# Regulator.net
KiCad netlist of a schematic drawn in Altium Designer
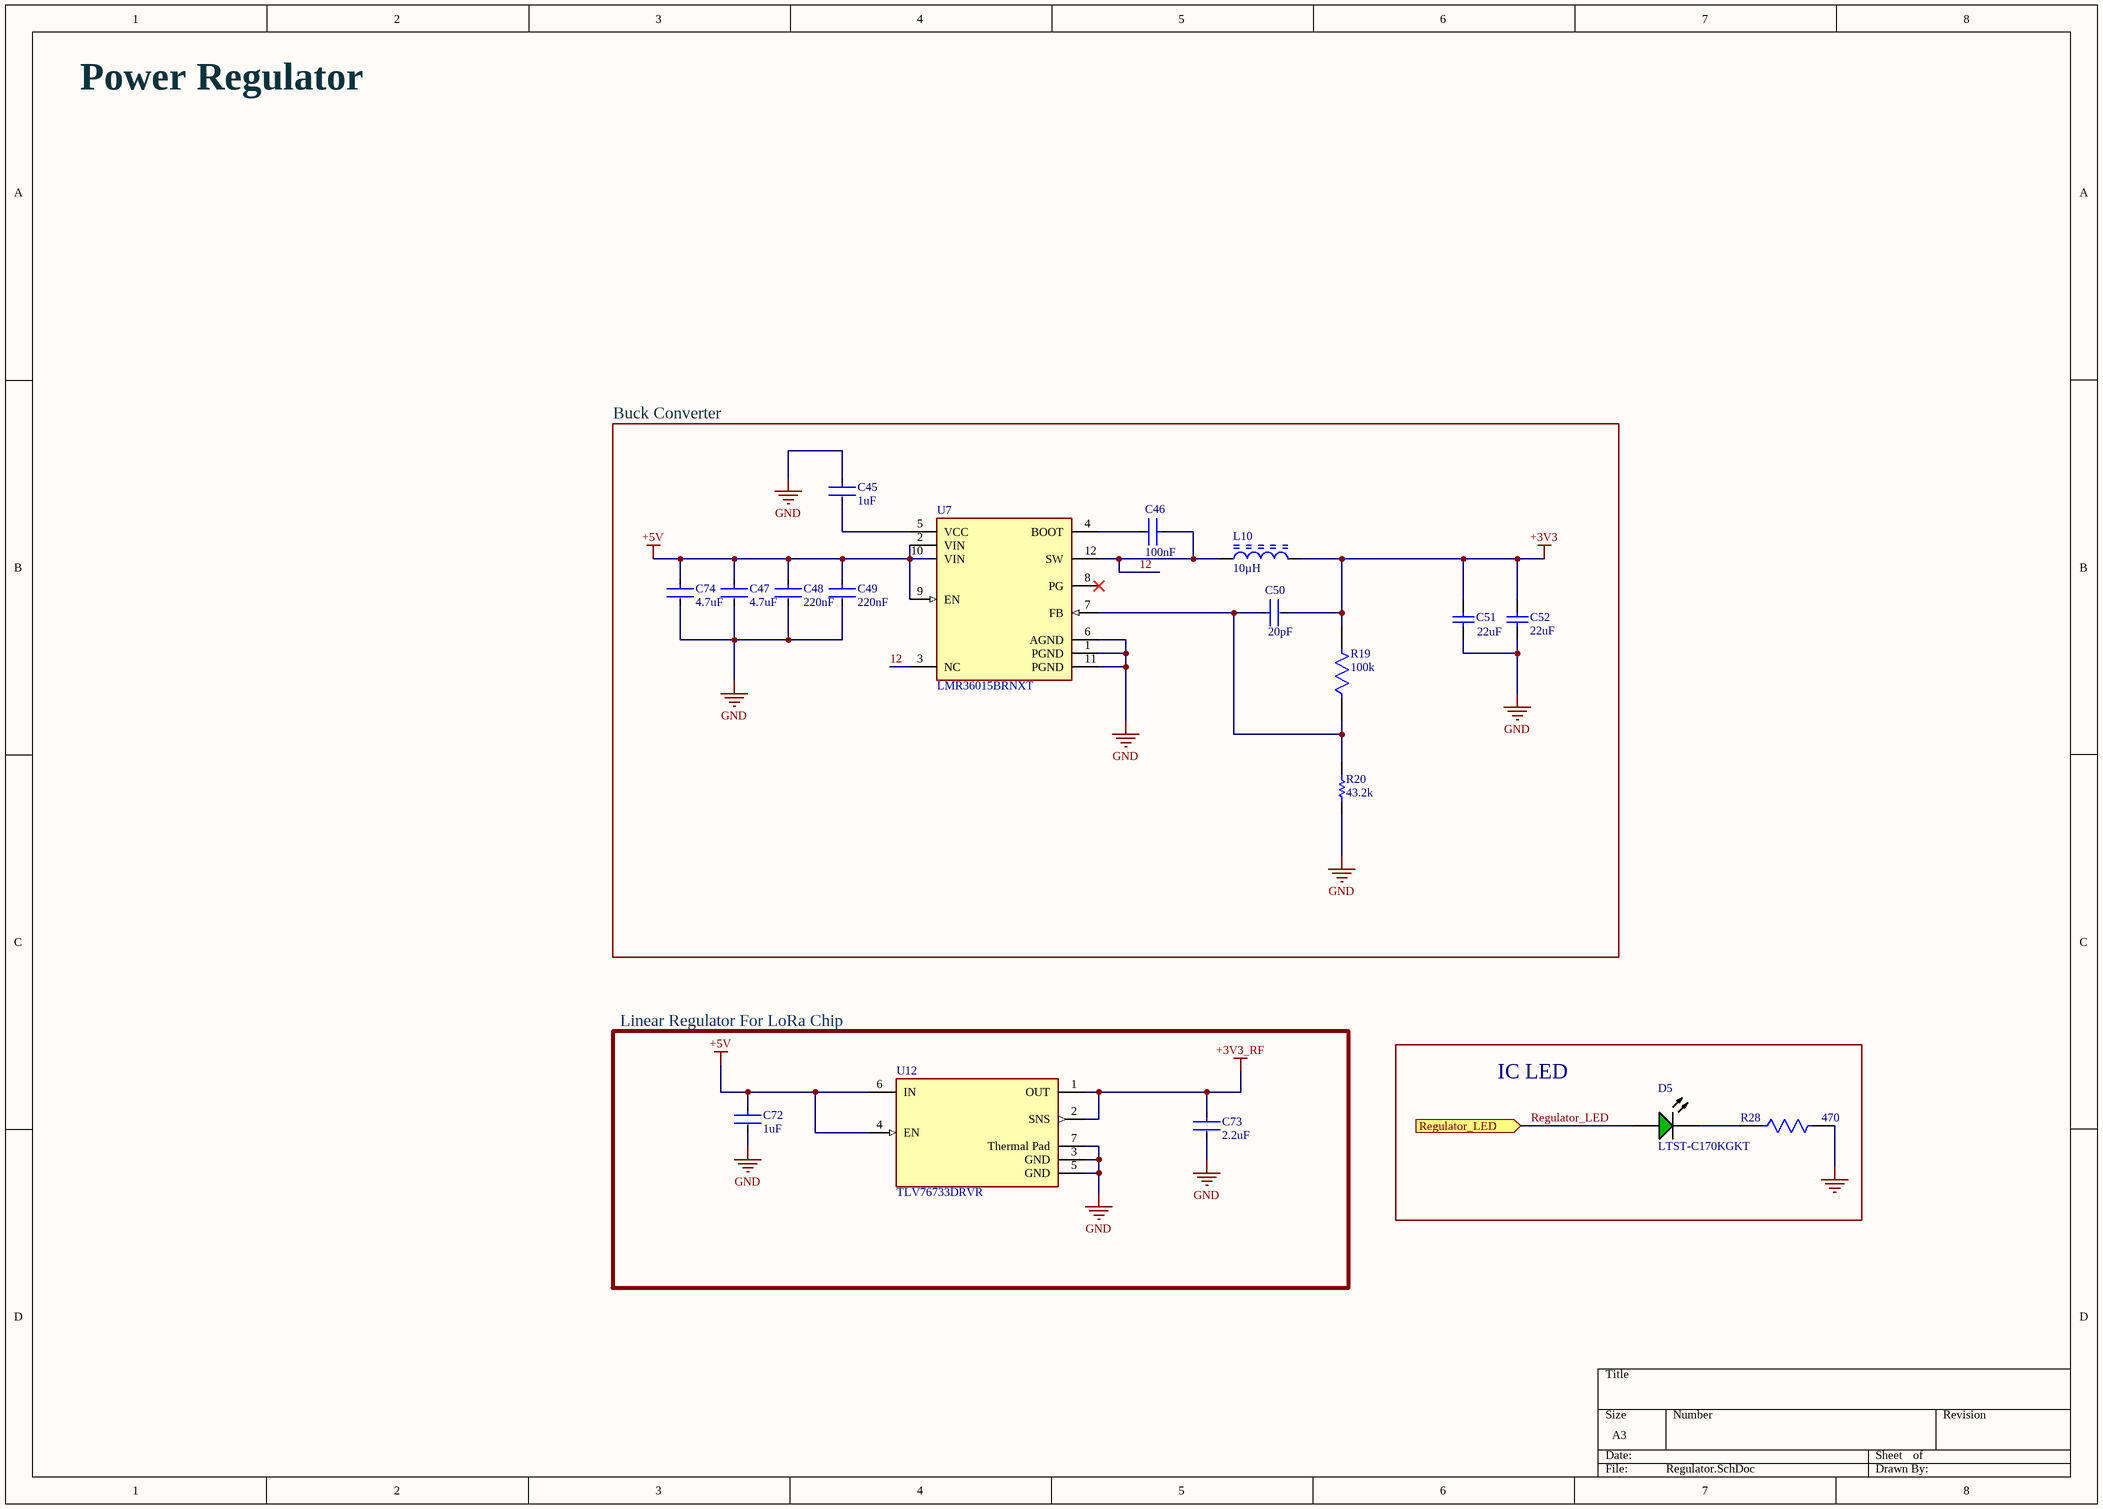
[diagram p0: Regulator.SchDoc]

(export (version "E")
  (design (tool "Eeschema 10.0.6"))
  (components
    (comp (ref "C45")
      (value "1uF")
      (footprint "FP-C0603C105K4PACTU-MFG")
      (description "CAP CER 1UF 16V X5R 0603")
      (fields (field (name "TOLERANCE") "10%") (field (name "VOLTAGE") "16V"))
      (libsource (lib "Altium Content Vault") (part "b4654b650e69147ec39a6b967a45e02"))
    )
    (comp (ref "C46")
      (value "100nF")
      (footprint "FP-GRM15-MFG")
      (description "CAP CER 0.1UF 16V X7R 0402")
      (fields (field (name "MANUFACTURER PART NUMBER") "GRM155R71C104KA88D") (field (name "TOLERANCE") "10%"))
      (libsource (lib "Altium Content Vault") (part "236180d848d6139a670b325ea6854c9"))
    )
    (comp (ref "C47")
      (value "4.7uF")
      (footprint "FP-1210-L_3_3_0_4-W_2_5_0-IPC_B")
      (description "Automotive Ceramic Capacitor, 1210, 4.7uF, 10%, X7R, 15%, 16V")
      (fields (field (name "TOLERANCE") "10%"))
      (libsource (lib "Altium Content Vault") (part "02cd4be3c70576c341d710602a673aa"))
    )
    (comp (ref "C48")
      (value "220nF")
      (footprint "FP-GRM155-0_05-IPC_C")
      (description "Chip Multilayer Ceramic Capacitors for General Purpose, 0402, 0.22uF, X7R, 15%, 10%, 16V")
      (fields (field (name "VOLTAGE") "16V") (field (name "TOLERANCE") "10%"))
      (libsource (lib "Altium Content Vault") (part "02cd4be3c70576c341d710602a673aa"))
    )
    (comp (ref "C49")
      (value "220nF")
      (footprint "FP-GRM155-0_05-IPC_C")
      (description "Chip Multilayer Ceramic Capacitors for General Purpose, 0402, 0.22uF, X7R, 15%, 10%, 16V")
      (fields (field (name "VOLTAGE") "16V") (field (name "TOLERANCE") "10%"))
      (libsource (lib "Altium Content Vault") (part "02cd4be3c70576c341d710602a673aa"))
    )
    (comp (ref "C50")
      (value "20pF")
      (footprint "FP-GJM022-0_02-IPC_B")
      (description "Ceramic Capacitor 20pF ±5% 16V C0G 01005 (0402 Metric)")
      (fields (field (name "TOLERANCE") "5%"))
      (libsource (lib "Altium Content Vault") (part "02cd4be3c70576c341d710602a673aa"))
    )
    (comp (ref "C51")
      (value "22uF")
      (footprint "MURA-1210_H_2.7_L")
      (fields (field (name "MANUFACTURER") "Murata") (field (name "TOLERANCE") "±10%"))
      (libsource (lib "Altium Content Vault") (part "CAP-NP-2"))
    )
    (comp (ref "C52")
      (value "22uF")
      (footprint "MURA-1210_H_2.7_L")
      (fields (field (name "MANUFACTURER") "Murata") (field (name "TOLERANCE") "±10%"))
      (libsource (lib "Altium Content Vault") (part "CAP-NP-2"))
    )
    (comp (ref "C72")
      (value "1uF")
      (footprint "FP-C0603C105K4PACTU-MFG")
      (description "CAP CER 1UF 16V X5R 0603")
      (fields (field (name "TOLERANCE") "10%") (field (name "VOLTAGE") "16V"))
      (libsource (lib "Altium Content Vault") (part "b4654b650e69147ec39a6b967a45e02"))
    )
    (comp (ref "C73")
      (value "2.2uF")
      (footprint "FP-C1608-080-0_1-IPC_C")
      (description "Multilayer Ceramic Capacitors 2.2μF ±10% 16V X5R SMD 0603")
      (fields (field (name "VOLTAGE") "16V") (field (name "TOLERANCE") "10%"))
      (libsource (lib "Altium Content Vault") (part "236180d848d6139a670b325ea6854c9"))
    )
    (comp (ref "C74")
      (value "4.7uF")
      (footprint "FP-1210-L_3_3_0_4-W_2_5_0-IPC_B")
      (description "Automotive Ceramic Capacitor, 1210, 4.7uF, 10%, X7R, 15%, 16V")
      (fields (field (name "TOLERANCE") "10%"))
      (libsource (lib "Altium Content Vault") (part "02cd4be3c70576c341d710602a673aa"))
    )
    (comp (ref "D5")
      (value "LTST-C170KGKT")
      (footprint "LTST-LTST-C170KGKT-2_V")
      (description "Ultra Bright AlInGaP Chip LED, 75 mW, -55 to 85 degC, 2-Pin SMD (0805), RoHS, Tape and Reel")
      (fields (field (name "MANUFACTURER") "Lite-On"))
      (libsource (lib "Altium Content Vault") (part "LED-GREEN-KA-2"))
    )
    (comp (ref "L10")
      (value "CM322522-100KL")
      (footprint "BOUR-CM322522_V")
      (description "Chip Inductor, 10 uH, +/- 10%, -40 to 125 degC, 1210 (3225 Metric), RoHS, Tape and Reel")
      (fields
        (field (name "INDUCTANCE") "10µH")
        (field (name "MANUFACTURER") "Bourns")
        (field (name "TOLERANCE") "10%")
      )
      (libsource (lib "Personal Repository") (part "BOUR-IND-2A"))
    )
    (comp (ref "R19")
      (value "100k")
      (footprint "FP-CRCW0402-C-e3-MFG")
      (description "RES 100K OHM 1% 1/16W 0402")
      (fields (field (name "TOLERANCE") "1%"))
      (libsource (lib "Altium Content Vault") (part "1029c3af85768c4190bb7ad29bc67b5"))
    )
    (comp (ref "R20")
      (value "43.2k")
      (footprint "RESC1005X40X25NL05T05")
      (fields (field (name "PART NUMBER") "CRCW040243K2FKED") (field (name "MANUFACTURER") "Vishay Dale"))
      (libsource (lib "Altium Content Vault") (part "RES"))
    )
    (comp (ref "R28")
      (value "470")
      (footprint "FP-CPF0603-MFG")
      (description "RES SMD 470Ω 0.1% 1/16W 0603\r\n\r\nCPF0603B470RE")
      (fields
        (field (name "MANUFACTURER") "TE Connectivity")
        (field (name "MANUFACTURER PART NUMBER") "CPF0603B470RE")
      )
      (libsource (lib "Altium Content Vault") (part "1029c3af85768c4190bb7ad29bc67b5"))
    )
    (comp (ref "U7")
      (value "LMR36015BRNXT")
      (footprint "FP-RNX0012B-MFG")
      (description "IC REGULATOR BUCK")
      (libsource (lib "Altium Content Vault") (part "99e4bd940d99564b2ae52ecd99d70d2"))
    )
    (comp (ref "U12")
      (value "TLV76733DRVR")
      (footprint "FP-DRV0006A-IPC_C")
      (description "VOLTAGE COMPARATOR")
      (libsource (lib "Altium Content Vault") (part "527f072e48108a7b9f646086bfc5874"))
    )
  )
  (nets
    (net (code "1") (name "+3V3") (class "Default")
      (node (ref "C50") (pin "2") (pinfunction "2_2") (pintype "passive"))
      (node (ref "C51") (pin "2") (pinfunction "2_2") (pintype "passive"))
      (node (ref "C52") (pin "2") (pinfunction "2_2") (pintype "passive"))
      (node (ref "L10") (pin "2") (pinfunction "2_2") (pintype "passive"))
      (node (ref "R19") (pin "2") (pinfunction "2_2") (pintype "passive"))
    )
    (net (code "2") (name "+3V3_RF") (class "Default")
      (node (ref "C73") (pin "2") (pinfunction "2_2") (pintype "passive"))
      (node (ref "U12") (pin "1") (pinfunction "OUT_1") (pintype "passive"))
      (node (ref "U12") (pin "2") (pinfunction "SNS_2") (pintype "output"))
    )
    (net (code "3") (name "+5V") (class "Default")
      (node (ref "C47") (pin "1") (pinfunction "1_1") (pintype "passive"))
      (node (ref "C48") (pin "1") (pinfunction "1_1") (pintype "passive"))
      (node (ref "C49") (pin "1") (pinfunction "1_1") (pintype "passive"))
      (node (ref "C72") (pin "1") (pinfunction "1_1") (pintype "passive"))
      (node (ref "C74") (pin "1") (pinfunction "1_1") (pintype "passive"))
      (node (ref "U12") (pin "4") (pinfunction "EN_4") (pintype "input"))
      (node (ref "U12") (pin "6") (pinfunction "IN_6") (pintype "power_in"))
      (node (ref "U7") (pin "10") (pinfunction "VIN_10") (pintype "power_in"))
      (node (ref "U7") (pin "2") (pinfunction "VIN_2") (pintype "power_in"))
      (node (ref "U7") (pin "9") (pinfunction "EN_9") (pintype "input"))
    )
    (net (code "4") (name "/12") (class "Default")
      (node (ref "C46") (pin "2") (pinfunction "2_2") (pintype "passive"))
      (node (ref "L10") (pin "1") (pinfunction "1_1") (pintype "passive"))
      (node (ref "U7") (pin "12") (pinfunction "SW_12") (pintype "passive"))
      (node (ref "U7") (pin "3") (pinfunction "NC_3") (pintype "passive"))
    )
    (net (code "5") (name "/Regulator_LED") (class "Default")
      (node (ref "D5") (pin "2") (pinfunction "A_2") (pintype "passive"))
    )
    (net (code "6") (name "GND") (class "Default")
      (node (ref "C45") (pin "1") (pinfunction "1_1") (pintype "passive"))
      (node (ref "C47") (pin "2") (pinfunction "2_2") (pintype "passive"))
      (node (ref "C48") (pin "2") (pinfunction "2_2") (pintype "passive"))
      (node (ref "C49") (pin "2") (pinfunction "2_2") (pintype "passive"))
      (node (ref "C51") (pin "1") (pinfunction "1_1") (pintype "passive"))
      (node (ref "C52") (pin "1") (pinfunction "1_1") (pintype "passive"))
      (node (ref "C72") (pin "2") (pinfunction "2_2") (pintype "passive"))
      (node (ref "C73") (pin "1") (pinfunction "1_1") (pintype "passive"))
      (node (ref "C74") (pin "2") (pinfunction "2_2") (pintype "passive"))
      (node (ref "R20") (pin "1") (pinfunction "1_1") (pintype "passive"))
      (node (ref "R28") (pin "2") (pinfunction "2_2") (pintype "passive"))
      (node (ref "U12") (pin "3") (pinfunction "GND_3") (pintype "power_in"))
      (node (ref "U12") (pin "5") (pinfunction "GND_5") (pintype "power_in"))
      (node (ref "U12") (pin "7") (pinfunction "Thermal_Pad_7") (pintype "passive"))
      (node (ref "U7") (pin "1") (pinfunction "PGND_1") (pintype "power_in"))
      (node (ref "U7") (pin "11") (pinfunction "PGND_11") (pintype "power_in"))
      (node (ref "U7") (pin "6") (pinfunction "AGND_6") (pintype "power_in"))
    )
    (net (code "7") (name "Net-(D5-K)") (class "Default")
      (node (ref "D5") (pin "1") (pinfunction "K_1") (pintype "passive"))
      (node (ref "R28") (pin "1") (pinfunction "1_1") (pintype "passive"))
    )
    (net (code "8") (name "Net-(U7-BOOT)") (class "Default")
      (node (ref "C46") (pin "1") (pinfunction "1_1") (pintype "passive"))
      (node (ref "U7") (pin "4") (pinfunction "BOOT_4") (pintype "passive"))
    )
    (net (code "9") (name "Net-(U7-FB)") (class "Default")
      (node (ref "C50") (pin "1") (pinfunction "1_1") (pintype "passive"))
      (node (ref "R19") (pin "1") (pinfunction "1_1") (pintype "passive"))
      (node (ref "R20") (pin "2") (pinfunction "2_2") (pintype "passive"))
      (node (ref "U7") (pin "7") (pinfunction "FB_7") (pintype "input"))
    )
    (net (code "10") (name "Net-(U7-VCC)") (class "Default")
      (node (ref "C45") (pin "2") (pinfunction "2_2") (pintype "passive"))
      (node (ref "U7") (pin "5") (pinfunction "VCC_5") (pintype "power_in"))
    )
    (net (code "11") (name "unconnected-(U7-PG-Pad8)") (class "Default")
      (node (ref "U7") (pin "8") (pinfunction "PG_8") (pintype "open_collector+no_connect"))
    )
  )
)
